# 08_RAM.net
KiCad netlist of a schematic drawn in Altium Designer
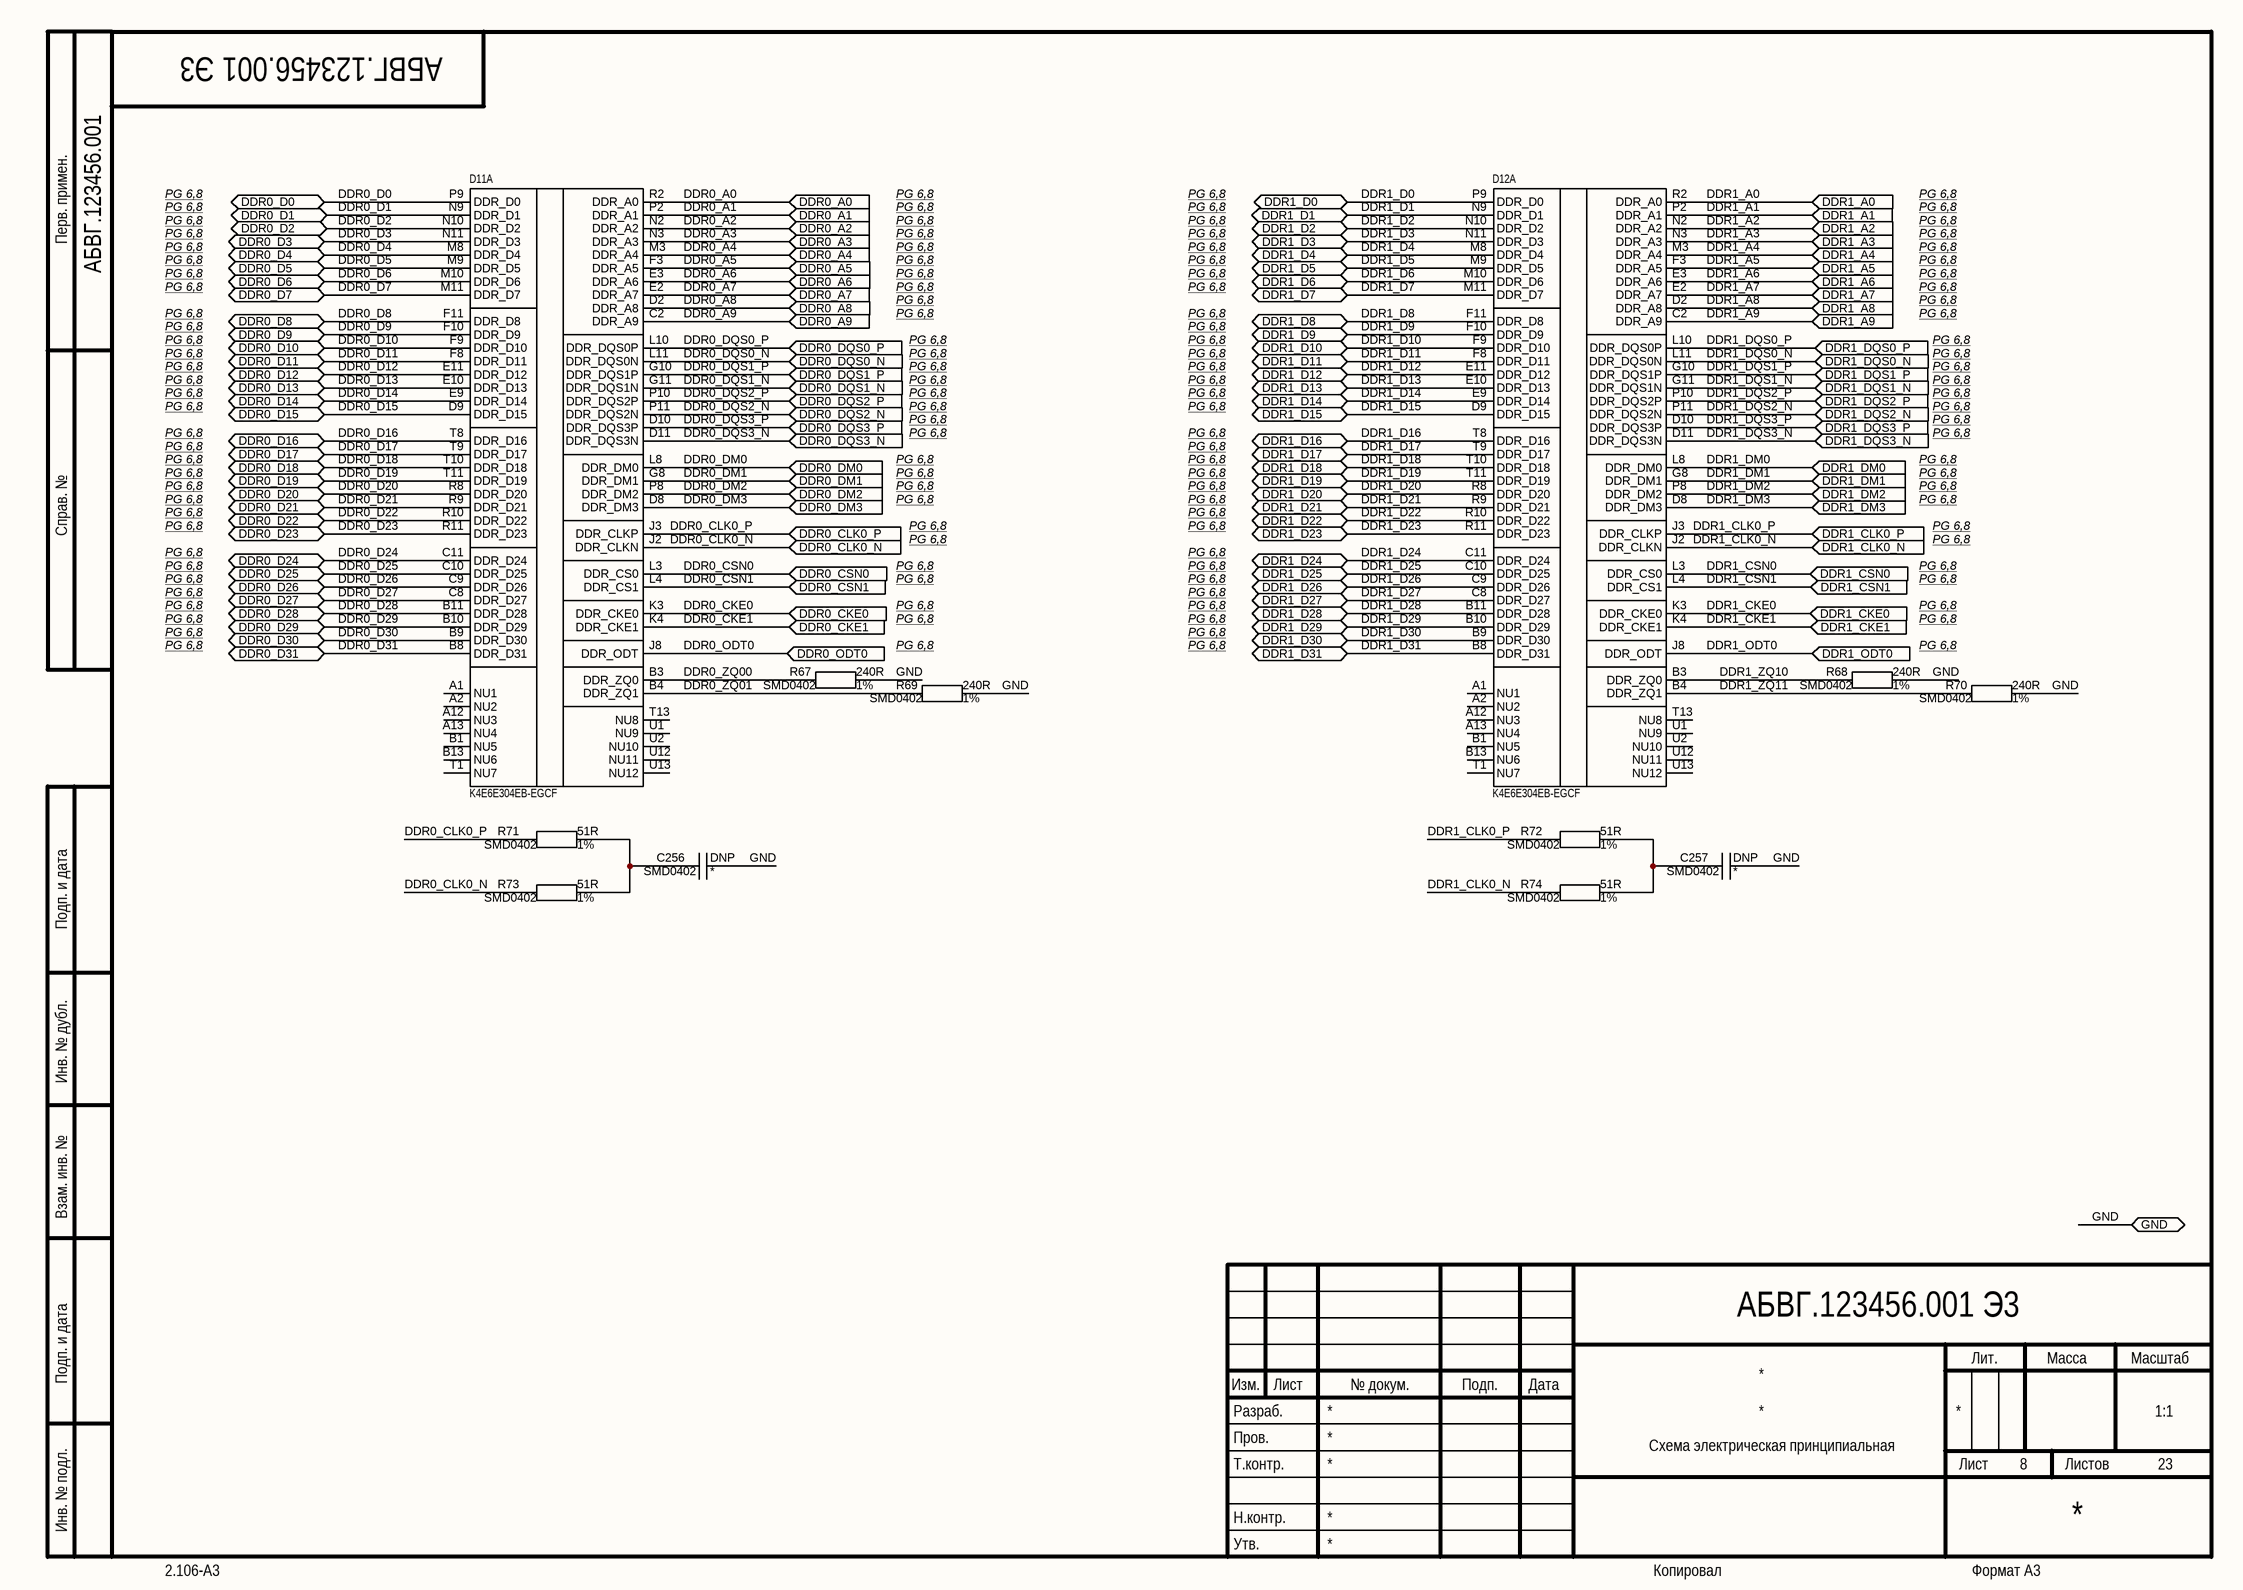
[diagram p0: 08 RAM.SchDoc]

(export (version "E")
  (design (tool "Eeschema 10.0.6"))
  (components
    (comp (ref "C256")
      (value "DNP")
      (footprint "Didur_PcbLib_1:CAP_SMD_0402_small")
      (fields
        (field (name "PACKAGE") "SMD0402")
        (field (name "PARTNUMBER") "Do Not Place")
        (field (name "VOLTAGE") "*")
      )
      (libsource (lib "Didur_SchLib_1") (part "Ceramic_Cap"))
    )
    (comp (ref "C257")
      (value "DNP")
      (footprint "Didur_PcbLib_1:CAP_SMD_0402_small")
      (fields
        (field (name "PACKAGE") "SMD0402")
        (field (name "PARTNUMBER") "Do Not Place")
        (field (name "VOLTAGE") "*")
      )
      (libsource (lib "Didur_SchLib_1") (part "Ceramic_Cap"))
    )
    (comp (ref "D11")
      (value "K4E6E304EB-EGCF")
      (footprint "Didur_PcbLib_1:FBGA178_13R00X11R50X1R20")
      (libsource (lib "Didur_SchLib_1") (part "K4E8E304EE-EGCE"))
    )
    (comp (ref "D12")
      (value "K4E6E304EB-EGCF")
      (footprint "Didur_PcbLib_1:FBGA178_13R00X11R50X1R20")
      (libsource (lib "Didur_SchLib_1") (part "K4E8E304EE-EGCE"))
    )
    (comp (ref "R67")
      (value "240R")
      (footprint "Didur_PcbLib_1:RES_SMD_0402_SMALL")
      (fields
        (field (name "PACKAGE") "SMD0402")
        (field (name "PARTNUMBER") "RC0402FR-07240RL")
        (field (name "TOLERANCE") "1%")
      )
      (libsource (lib "Didur_SchLib_1") (part "Chip_Res"))
    )
    (comp (ref "R68")
      (value "240R")
      (footprint "Didur_PcbLib_1:RES_SMD_0402_SMALL")
      (fields
        (field (name "PACKAGE") "SMD0402")
        (field (name "PARTNUMBER") "RC0402FR-07240RL")
        (field (name "TOLERANCE") "1%")
      )
      (libsource (lib "Didur_SchLib_1") (part "Chip_Res"))
    )
    (comp (ref "R69")
      (value "240R")
      (footprint "Didur_PcbLib_1:RES_SMD_0402_SMALL")
      (fields
        (field (name "PACKAGE") "SMD0402")
        (field (name "PARTNUMBER") "RC0402FR-07240RL")
        (field (name "TOLERANCE") "1%")
      )
      (libsource (lib "Didur_SchLib_1") (part "Chip_Res"))
    )
    (comp (ref "R70")
      (value "240R")
      (footprint "Didur_PcbLib_1:RES_SMD_0402_SMALL")
      (fields
        (field (name "PACKAGE") "SMD0402")
        (field (name "PARTNUMBER") "RC0402FR-07240RL")
        (field (name "TOLERANCE") "1%")
      )
      (libsource (lib "Didur_SchLib_1") (part "Chip_Res"))
    )
    (comp (ref "R71")
      (value "51R")
      (footprint "Didur_PcbLib_1:RES_SMD_0402_SMALL")
      (fields
        (field (name "PACKAGE") "SMD0402")
        (field (name "PARTNUMBER") "RC0402FR-0751RL")
        (field (name "TOLERANCE") "1%")
      )
      (libsource (lib "Didur_SchLib_1") (part "Chip_Res"))
    )
    (comp (ref "R72")
      (value "51R")
      (footprint "Didur_PcbLib_1:RES_SMD_0402_SMALL")
      (fields
        (field (name "PACKAGE") "SMD0402")
        (field (name "PARTNUMBER") "RC0402FR-0751RL")
        (field (name "TOLERANCE") "1%")
      )
      (libsource (lib "Didur_SchLib_1") (part "Chip_Res"))
    )
    (comp (ref "R73")
      (value "51R")
      (footprint "Didur_PcbLib_1:RES_SMD_0402_SMALL")
      (fields
        (field (name "PACKAGE") "SMD0402")
        (field (name "PARTNUMBER") "RC0402FR-0751RL")
        (field (name "TOLERANCE") "1%")
      )
      (libsource (lib "Didur_SchLib_1") (part "Chip_Res"))
    )
    (comp (ref "R74")
      (value "51R")
      (footprint "Didur_PcbLib_1:RES_SMD_0402_SMALL")
      (fields
        (field (name "PACKAGE") "SMD0402")
        (field (name "PARTNUMBER") "RC0402FR-0751RL")
        (field (name "TOLERANCE") "1%")
      )
      (libsource (lib "Didur_SchLib_1") (part "Chip_Res"))
    )
  )
  (nets
    (net (code "1") (name "/DDR0_A0") (class "Default")
      (node (ref "D11") (pin "R2") (pinfunction "DDR_A0_R2") (pintype "passive"))
    )
    (net (code "2") (name "/DDR0_A1") (class "Default")
      (node (ref "D11") (pin "P2") (pinfunction "DDR_A1_P2") (pintype "passive"))
    )
    (net (code "3") (name "/DDR0_A2") (class "Default")
      (node (ref "D11") (pin "N2") (pinfunction "DDR_A2_N2") (pintype "passive"))
    )
    (net (code "4") (name "/DDR0_A3") (class "Default")
      (node (ref "D11") (pin "N3") (pinfunction "DDR_A3_N3") (pintype "passive"))
    )
    (net (code "5") (name "/DDR0_A4") (class "Default")
      (node (ref "D11") (pin "M3") (pinfunction "DDR_A4_M3") (pintype "passive"))
    )
    (net (code "6") (name "/DDR0_A5") (class "Default")
      (node (ref "D11") (pin "F3") (pinfunction "DDR_A5_F3") (pintype "passive"))
    )
    (net (code "7") (name "/DDR0_A6") (class "Default")
      (node (ref "D11") (pin "E3") (pinfunction "DDR_A6_E3") (pintype "passive"))
    )
    (net (code "8") (name "/DDR0_A7") (class "Default")
      (node (ref "D11") (pin "E2") (pinfunction "DDR_A7_E2") (pintype "passive"))
    )
    (net (code "9") (name "/DDR0_A8") (class "Default")
      (node (ref "D11") (pin "D2") (pinfunction "DDR_A8_D2") (pintype "passive"))
    )
    (net (code "10") (name "/DDR0_A9") (class "Default")
      (node (ref "D11") (pin "C2") (pinfunction "DDR_A9_C2") (pintype "passive"))
    )
    (net (code "11") (name "/DDR0_CKE0") (class "Default")
      (node (ref "D11") (pin "K3") (pinfunction "DDR_CKE0_K3") (pintype "passive"))
    )
    (net (code "12") (name "/DDR0_CKE1") (class "Default")
      (node (ref "D11") (pin "K4") (pinfunction "DDR_CKE1_K4") (pintype "passive"))
    )
    (net (code "13") (name "/DDR0_CLK0_N") (class "Default")
      (node (ref "D11") (pin "J2") (pinfunction "DDR_CLKN_J2") (pintype "passive"))
      (node (ref "R73") (pin "2") (pinfunction "2_2") (pintype "passive"))
    )
    (net (code "14") (name "/DDR0_CLK0_P") (class "Default")
      (node (ref "D11") (pin "J3") (pinfunction "DDR_CLKP_J3") (pintype "passive"))
      (node (ref "R71") (pin "2") (pinfunction "2_2") (pintype "passive"))
    )
    (net (code "15") (name "/DDR0_CSN0") (class "Default")
      (node (ref "D11") (pin "L3") (pinfunction "DDR_CS0_L3") (pintype "passive"))
    )
    (net (code "16") (name "/DDR0_CSN1") (class "Default")
      (node (ref "D11") (pin "L4") (pinfunction "DDR_CS1_L4") (pintype "passive"))
    )
    (net (code "17") (name "/DDR0_D0") (class "Default")
      (node (ref "D11") (pin "P9") (pinfunction "DDR_D0_P9") (pintype "passive"))
    )
    (net (code "18") (name "/DDR0_D1") (class "Default")
      (node (ref "D11") (pin "N9") (pinfunction "DDR_D1_N9") (pintype "passive"))
    )
    (net (code "19") (name "/DDR0_D2") (class "Default")
      (node (ref "D11") (pin "N10") (pinfunction "DDR_D2_N10") (pintype "passive"))
    )
    (net (code "20") (name "/DDR0_D3") (class "Default")
      (node (ref "D11") (pin "N11") (pinfunction "DDR_D3_N11") (pintype "passive"))
    )
    (net (code "21") (name "/DDR0_D4") (class "Default")
      (node (ref "D11") (pin "M8") (pinfunction "DDR_D4_M8") (pintype "passive"))
    )
    (net (code "22") (name "/DDR0_D5") (class "Default")
      (node (ref "D11") (pin "M9") (pinfunction "DDR_D5_M9") (pintype "passive"))
    )
    (net (code "23") (name "/DDR0_D6") (class "Default")
      (node (ref "D11") (pin "M10") (pinfunction "DDR_D6_M10") (pintype "passive"))
    )
    (net (code "24") (name "/DDR0_D7") (class "Default")
      (node (ref "D11") (pin "M11") (pinfunction "DDR_D7_M11") (pintype "passive"))
    )
    (net (code "25") (name "/DDR0_D8") (class "Default")
      (node (ref "D11") (pin "F11") (pinfunction "DDR_D8_F11") (pintype "passive"))
    )
    (net (code "26") (name "/DDR0_D9") (class "Default")
      (node (ref "D11") (pin "F10") (pinfunction "DDR_D9_F10") (pintype "passive"))
    )
    (net (code "27") (name "/DDR0_D10") (class "Default")
      (node (ref "D11") (pin "F9") (pinfunction "DDR_D10_F9") (pintype "passive"))
    )
    (net (code "28") (name "/DDR0_D11") (class "Default")
      (node (ref "D11") (pin "F8") (pinfunction "DDR_D11_F8") (pintype "passive"))
    )
    (net (code "29") (name "/DDR0_D12") (class "Default")
      (node (ref "D11") (pin "E11") (pinfunction "DDR_D12_E11") (pintype "passive"))
    )
    (net (code "30") (name "/DDR0_D13") (class "Default")
      (node (ref "D11") (pin "E10") (pinfunction "DDR_D13_E10") (pintype "passive"))
    )
    (net (code "31") (name "/DDR0_D14") (class "Default")
      (node (ref "D11") (pin "E9") (pinfunction "DDR_D14_E9") (pintype "passive"))
    )
    (net (code "32") (name "/DDR0_D15") (class "Default")
      (node (ref "D11") (pin "D9") (pinfunction "DDR_D15_D9") (pintype "passive"))
    )
    (net (code "33") (name "/DDR0_D16") (class "Default")
      (node (ref "D11") (pin "T8") (pinfunction "DDR_D16_T8") (pintype "passive"))
    )
    (net (code "34") (name "/DDR0_D17") (class "Default")
      (node (ref "D11") (pin "T9") (pinfunction "DDR_D17_T9") (pintype "passive"))
    )
    (net (code "35") (name "/DDR0_D18") (class "Default")
      (node (ref "D11") (pin "T10") (pinfunction "DDR_D18_T10") (pintype "passive"))
    )
    (net (code "36") (name "/DDR0_D19") (class "Default")
      (node (ref "D11") (pin "T11") (pinfunction "DDR_D19_T11") (pintype "passive"))
    )
    (net (code "37") (name "/DDR0_D20") (class "Default")
      (node (ref "D11") (pin "R8") (pinfunction "DDR_D20_R8") (pintype "passive"))
    )
    (net (code "38") (name "/DDR0_D21") (class "Default")
      (node (ref "D11") (pin "R9") (pinfunction "DDR_D21_R9") (pintype "passive"))
    )
    (net (code "39") (name "/DDR0_D22") (class "Default")
      (node (ref "D11") (pin "R10") (pinfunction "DDR_D22_R10") (pintype "passive"))
    )
    (net (code "40") (name "/DDR0_D23") (class "Default")
      (node (ref "D11") (pin "R11") (pinfunction "DDR_D23_R11") (pintype "passive"))
    )
    (net (code "41") (name "/DDR0_D24") (class "Default")
      (node (ref "D11") (pin "C11") (pinfunction "DDR_D24_C11") (pintype "passive"))
    )
    (net (code "42") (name "/DDR0_D25") (class "Default")
      (node (ref "D11") (pin "C10") (pinfunction "DDR_D25_C10") (pintype "passive"))
    )
    (net (code "43") (name "/DDR0_D26") (class "Default")
      (node (ref "D11") (pin "C9") (pinfunction "DDR_D26_C9") (pintype "passive"))
    )
    (net (code "44") (name "/DDR0_D27") (class "Default")
      (node (ref "D11") (pin "C8") (pinfunction "DDR_D27_C8") (pintype "passive"))
    )
    (net (code "45") (name "/DDR0_D28") (class "Default")
      (node (ref "D11") (pin "B11") (pinfunction "DDR_D28_B11") (pintype "passive"))
    )
    (net (code "46") (name "/DDR0_D29") (class "Default")
      (node (ref "D11") (pin "B10") (pinfunction "DDR_D29_B10") (pintype "passive"))
    )
    (net (code "47") (name "/DDR0_D30") (class "Default")
      (node (ref "D11") (pin "B9") (pinfunction "DDR_D30_B9") (pintype "passive"))
    )
    (net (code "48") (name "/DDR0_D31") (class "Default")
      (node (ref "D11") (pin "B8") (pinfunction "DDR_D31_B8") (pintype "passive"))
    )
    (net (code "49") (name "/DDR0_DM0") (class "Default")
      (node (ref "D11") (pin "L8") (pinfunction "DDR_DM0_L8") (pintype "passive"))
    )
    (net (code "50") (name "/DDR0_DM1") (class "Default")
      (node (ref "D11") (pin "G8") (pinfunction "DDR_DM1_G8") (pintype "passive"))
    )
    (net (code "51") (name "/DDR0_DM2") (class "Default")
      (node (ref "D11") (pin "P8") (pinfunction "DDR_DM2_P8") (pintype "passive"))
    )
    (net (code "52") (name "/DDR0_DM3") (class "Default")
      (node (ref "D11") (pin "D8") (pinfunction "DDR_DM3_D8") (pintype "passive"))
    )
    (net (code "53") (name "/DDR0_DQS0_N") (class "Default")
      (node (ref "D11") (pin "L11") (pinfunction "DDR_DQS0N_L11") (pintype "passive"))
    )
    (net (code "54") (name "/DDR0_DQS0_P") (class "Default")
      (node (ref "D11") (pin "L10") (pinfunction "DDR_DQS0P_L10") (pintype "passive"))
    )
    (net (code "55") (name "/DDR0_DQS1_N") (class "Default")
      (node (ref "D11") (pin "G11") (pinfunction "DDR_DQS1N_G11") (pintype "passive"))
    )
    (net (code "56") (name "/DDR0_DQS1_P") (class "Default")
      (node (ref "D11") (pin "G10") (pinfunction "DDR_DQS1P_G10") (pintype "passive"))
    )
    (net (code "57") (name "/DDR0_DQS2_N") (class "Default")
      (node (ref "D11") (pin "P11") (pinfunction "DDR_DQS2N_P11") (pintype "passive"))
    )
    (net (code "58") (name "/DDR0_DQS2_P") (class "Default")
      (node (ref "D11") (pin "P10") (pinfunction "DDR_DQS2P_P10") (pintype "passive"))
    )
    (net (code "59") (name "/DDR0_DQS3_N") (class "Default")
      (node (ref "D11") (pin "D11") (pinfunction "DDR_DQS3N_D11") (pintype "passive"))
    )
    (net (code "60") (name "/DDR0_DQS3_P") (class "Default")
      (node (ref "D11") (pin "D10") (pinfunction "DDR_DQS3P_D10") (pintype "passive"))
    )
    (net (code "61") (name "/DDR0_ODT0") (class "Default")
      (node (ref "D11") (pin "J8") (pinfunction "DDR_ODT_J8") (pintype "passive"))
    )
    (net (code "62") (name "/DDR0_ZQ00") (class "Default")
      (node (ref "D11") (pin "B3") (pinfunction "DDR_ZQ0_B3") (pintype "passive"))
      (node (ref "R67") (pin "2") (pinfunction "2_2") (pintype "passive"))
    )
    (net (code "63") (name "/DDR0_ZQ01") (class "Default")
      (node (ref "D11") (pin "B4") (pinfunction "DDR_ZQ1_B4") (pintype "passive"))
      (node (ref "R69") (pin "2") (pinfunction "2_2") (pintype "passive"))
    )
    (net (code "64") (name "/DDR1_A0") (class "Default")
      (node (ref "D12") (pin "R2") (pinfunction "DDR_A0_R2") (pintype "passive"))
    )
    (net (code "65") (name "/DDR1_A1") (class "Default")
      (node (ref "D12") (pin "P2") (pinfunction "DDR_A1_P2") (pintype "passive"))
    )
    (net (code "66") (name "/DDR1_A2") (class "Default")
      (node (ref "D12") (pin "N2") (pinfunction "DDR_A2_N2") (pintype "passive"))
    )
    (net (code "67") (name "/DDR1_A3") (class "Default")
      (node (ref "D12") (pin "N3") (pinfunction "DDR_A3_N3") (pintype "passive"))
    )
    (net (code "68") (name "/DDR1_A4") (class "Default")
      (node (ref "D12") (pin "M3") (pinfunction "DDR_A4_M3") (pintype "passive"))
    )
    (net (code "69") (name "/DDR1_A5") (class "Default")
      (node (ref "D12") (pin "F3") (pinfunction "DDR_A5_F3") (pintype "passive"))
    )
    (net (code "70") (name "/DDR1_A6") (class "Default")
      (node (ref "D12") (pin "E3") (pinfunction "DDR_A6_E3") (pintype "passive"))
    )
    (net (code "71") (name "/DDR1_A7") (class "Default")
      (node (ref "D12") (pin "E2") (pinfunction "DDR_A7_E2") (pintype "passive"))
    )
    (net (code "72") (name "/DDR1_A8") (class "Default")
      (node (ref "D12") (pin "D2") (pinfunction "DDR_A8_D2") (pintype "passive"))
    )
    (net (code "73") (name "/DDR1_A9") (class "Default")
      (node (ref "D12") (pin "C2") (pinfunction "DDR_A9_C2") (pintype "passive"))
    )
    (net (code "74") (name "/DDR1_CKE0") (class "Default")
      (node (ref "D12") (pin "K3") (pinfunction "DDR_CKE0_K3") (pintype "passive"))
    )
    (net (code "75") (name "/DDR1_CKE1") (class "Default")
      (node (ref "D12") (pin "K4") (pinfunction "DDR_CKE1_K4") (pintype "passive"))
    )
    (net (code "76") (name "/DDR1_CLK0_N") (class "Default")
      (node (ref "D12") (pin "J2") (pinfunction "DDR_CLKN_J2") (pintype "passive"))
      (node (ref "R74") (pin "2") (pinfunction "2_2") (pintype "passive"))
    )
    (net (code "77") (name "/DDR1_CLK0_P") (class "Default")
      (node (ref "D12") (pin "J3") (pinfunction "DDR_CLKP_J3") (pintype "passive"))
      (node (ref "R72") (pin "2") (pinfunction "2_2") (pintype "passive"))
    )
    (net (code "78") (name "/DDR1_CSN0") (class "Default")
      (node (ref "D12") (pin "L3") (pinfunction "DDR_CS0_L3") (pintype "passive"))
    )
    (net (code "79") (name "/DDR1_CSN1") (class "Default")
      (node (ref "D12") (pin "L4") (pinfunction "DDR_CS1_L4") (pintype "passive"))
    )
    (net (code "80") (name "/DDR1_D0") (class "Default")
      (node (ref "D12") (pin "P9") (pinfunction "DDR_D0_P9") (pintype "passive"))
    )
    (net (code "81") (name "/DDR1_D1") (class "Default")
      (node (ref "D12") (pin "N9") (pinfunction "DDR_D1_N9") (pintype "passive"))
    )
    (net (code "82") (name "/DDR1_D2") (class "Default")
      (node (ref "D12") (pin "N10") (pinfunction "DDR_D2_N10") (pintype "passive"))
    )
    (net (code "83") (name "/DDR1_D3") (class "Default")
      (node (ref "D12") (pin "N11") (pinfunction "DDR_D3_N11") (pintype "passive"))
    )
    (net (code "84") (name "/DDR1_D4") (class "Default")
      (node (ref "D12") (pin "M8") (pinfunction "DDR_D4_M8") (pintype "passive"))
    )
    (net (code "85") (name "/DDR1_D5") (class "Default")
      (node (ref "D12") (pin "M9") (pinfunction "DDR_D5_M9") (pintype "passive"))
    )
    (net (code "86") (name "/DDR1_D6") (class "Default")
      (node (ref "D12") (pin "M10") (pinfunction "DDR_D6_M10") (pintype "passive"))
    )
    (net (code "87") (name "/DDR1_D7") (class "Default")
      (node (ref "D12") (pin "M11") (pinfunction "DDR_D7_M11") (pintype "passive"))
    )
    (net (code "88") (name "/DDR1_D8") (class "Default")
      (node (ref "D12") (pin "F11") (pinfunction "DDR_D8_F11") (pintype "passive"))
    )
    (net (code "89") (name "/DDR1_D9") (class "Default")
      (node (ref "D12") (pin "F10") (pinfunction "DDR_D9_F10") (pintype "passive"))
    )
    (net (code "90") (name "/DDR1_D10") (class "Default")
      (node (ref "D12") (pin "F9") (pinfunction "DDR_D10_F9") (pintype "passive"))
    )
    (net (code "91") (name "/DDR1_D11") (class "Default")
      (node (ref "D12") (pin "F8") (pinfunction "DDR_D11_F8") (pintype "passive"))
    )
    (net (code "92") (name "/DDR1_D12") (class "Default")
      (node (ref "D12") (pin "E11") (pinfunction "DDR_D12_E11") (pintype "passive"))
    )
    (net (code "93") (name "/DDR1_D13") (class "Default")
      (node (ref "D12") (pin "E10") (pinfunction "DDR_D13_E10") (pintype "passive"))
    )
    (net (code "94") (name "/DDR1_D14") (class "Default")
      (node (ref "D12") (pin "E9") (pinfunction "DDR_D14_E9") (pintype "passive"))
    )
    (net (code "95") (name "/DDR1_D15") (class "Default")
      (node (ref "D12") (pin "D9") (pinfunction "DDR_D15_D9") (pintype "passive"))
    )
    (net (code "96") (name "/DDR1_D16") (class "Default")
      (node (ref "D12") (pin "T8") (pinfunction "DDR_D16_T8") (pintype "passive"))
    )
    (net (code "97") (name "/DDR1_D17") (class "Default")
      (node (ref "D12") (pin "T9") (pinfunction "DDR_D17_T9") (pintype "passive"))
    )
    (net (code "98") (name "/DDR1_D18") (class "Default")
      (node (ref "D12") (pin "T10") (pinfunction "DDR_D18_T10") (pintype "passive"))
    )
    (net (code "99") (name "/DDR1_D19") (class "Default")
      (node (ref "D12") (pin "T11") (pinfunction "DDR_D19_T11") (pintype "passive"))
    )
    (net (code "100") (name "/DDR1_D20") (class "Default")
      (node (ref "D12") (pin "R8") (pinfunction "DDR_D20_R8") (pintype "passive"))
    )
    (net (code "101") (name "/DDR1_D21") (class "Default")
      (node (ref "D12") (pin "R9") (pinfunction "DDR_D21_R9") (pintype "passive"))
    )
    (net (code "102") (name "/DDR1_D22") (class "Default")
      (node (ref "D12") (pin "R10") (pinfunction "DDR_D22_R10") (pintype "passive"))
    )
    (net (code "103") (name "/DDR1_D23") (class "Default")
      (node (ref "D12") (pin "R11") (pinfunction "DDR_D23_R11") (pintype "passive"))
    )
    (net (code "104") (name "/DDR1_D24") (class "Default")
      (node (ref "D12") (pin "C11") (pinfunction "DDR_D24_C11") (pintype "passive"))
    )
    (net (code "105") (name "/DDR1_D25") (class "Default")
      (node (ref "D12") (pin "C10") (pinfunction "DDR_D25_C10") (pintype "passive"))
    )
    (net (code "106") (name "/DDR1_D26") (class "Default")
      (node (ref "D12") (pin "C9") (pinfunction "DDR_D26_C9") (pintype "passive"))
    )
    (net (code "107") (name "/DDR1_D27") (class "Default")
      (node (ref "D12") (pin "C8") (pinfunction "DDR_D27_C8") (pintype "passive"))
    )
    (net (code "108") (name "/DDR1_D28") (class "Default")
      (node (ref "D12") (pin "B11") (pinfunction "DDR_D28_B11") (pintype "passive"))
    )
    (net (code "109") (name "/DDR1_D29") (class "Default")
      (node (ref "D12") (pin "B10") (pinfunction "DDR_D29_B10") (pintype "passive"))
    )
    (net (code "110") (name "/DDR1_D30") (class "Default")
      (node (ref "D12") (pin "B9") (pinfunction "DDR_D30_B9") (pintype "passive"))
    )
    (net (code "111") (name "/DDR1_D31") (class "Default")
      (node (ref "D12") (pin "B8") (pinfunction "DDR_D31_B8") (pintype "passive"))
    )
    (net (code "112") (name "/DDR1_DM0") (class "Default")
      (node (ref "D12") (pin "L8") (pinfunction "DDR_DM0_L8") (pintype "passive"))
    )
    (net (code "113") (name "/DDR1_DM1") (class "Default")
      (node (ref "D12") (pin "G8") (pinfunction "DDR_DM1_G8") (pintype "passive"))
    )
    (net (code "114") (name "/DDR1_DM2") (class "Default")
      (node (ref "D12") (pin "P8") (pinfunction "DDR_DM2_P8") (pintype "passive"))
    )
    (net (code "115") (name "/DDR1_DM3") (class "Default")
      (node (ref "D12") (pin "D8") (pinfunction "DDR_DM3_D8") (pintype "passive"))
    )
    (net (code "116") (name "/DDR1_DQS0_N") (class "Default")
      (node (ref "D12") (pin "L11") (pinfunction "DDR_DQS0N_L11") (pintype "passive"))
    )
    (net (code "117") (name "/DDR1_DQS0_P") (class "Default")
      (node (ref "D12") (pin "L10") (pinfunction "DDR_DQS0P_L10") (pintype "passive"))
    )
    (net (code "118") (name "/DDR1_DQS1_N") (class "Default")
      (node (ref "D12") (pin "G11") (pinfunction "DDR_DQS1N_G11") (pintype "passive"))
    )
    (net (code "119") (name "/DDR1_DQS1_P") (class "Default")
      (node (ref "D12") (pin "G10") (pinfunction "DDR_DQS1P_G10") (pintype "passive"))
    )
    (net (code "120") (name "/DDR1_DQS2_N") (class "Default")
      (node (ref "D12") (pin "P11") (pinfunction "DDR_DQS2N_P11") (pintype "passive"))
    )
    (net (code "121") (name "/DDR1_DQS2_P") (class "Default")
      (node (ref "D12") (pin "P10") (pinfunction "DDR_DQS2P_P10") (pintype "passive"))
    )
    (net (code "122") (name "/DDR1_DQS3_N") (class "Default")
      (node (ref "D12") (pin "D11") (pinfunction "DDR_DQS3N_D11") (pintype "passive"))
    )
    (net (code "123") (name "/DDR1_DQS3_P") (class "Default")
      (node (ref "D12") (pin "D10") (pinfunction "DDR_DQS3P_D10") (pintype "passive"))
    )
    (net (code "124") (name "/DDR1_ODT0") (class "Default")
      (node (ref "D12") (pin "J8") (pinfunction "DDR_ODT_J8") (pintype "passive"))
    )
    (net (code "125") (name "/DDR1_ZQ10") (class "Default")
      (node (ref "D12") (pin "B3") (pinfunction "DDR_ZQ0_B3") (pintype "passive"))
      (node (ref "R68") (pin "2") (pinfunction "2_2") (pintype "passive"))
    )
    (net (code "126") (name "/DDR1_ZQ11") (class "Default")
      (node (ref "D12") (pin "B4") (pinfunction "DDR_ZQ1_B4") (pintype "passive"))
      (node (ref "R70") (pin "2") (pinfunction "2_2") (pintype "passive"))
    )
    (net (code "127") (name "/GND") (class "Default")
      (node (ref "C256") (pin "1") (pinfunction "1_1") (pintype "power_in"))
      (node (ref "C257") (pin "1") (pinfunction "1_1") (pintype "power_in"))
      (node (ref "R67") (pin "1") (pinfunction "1_1") (pintype "passive"))
      (node (ref "R68") (pin "1") (pinfunction "1_1") (pintype "passive"))
      (node (ref "R69") (pin "1") (pinfunction "1_1") (pintype "passive"))
      (node (ref "R70") (pin "1") (pinfunction "1_1") (pintype "passive"))
    )
    (net (code "128") (name "Net-(C256-Pad2)") (class "Default")
      (node (ref "C256") (pin "2") (pinfunction "2_2") (pintype "power_in"))
      (node (ref "R71") (pin "1") (pinfunction "1_1") (pintype "passive"))
      (node (ref "R73") (pin "1") (pinfunction "1_1") (pintype "passive"))
    )
    (net (code "129") (name "Net-(C257-Pad2)") (class "Default")
      (node (ref "C257") (pin "2") (pinfunction "2_2") (pintype "power_in"))
      (node (ref "R72") (pin "1") (pinfunction "1_1") (pintype "passive"))
      (node (ref "R74") (pin "1") (pinfunction "1_1") (pintype "passive"))
    )
    (net (code "130") (name "unconnected-(D11A-NU1-PadA1)") (class "Default")
      (node (ref "D11") (pin "A1") (pinfunction "NU1_A1") (pintype "passive"))
    )
    (net (code "131") (name "unconnected-(D11A-NU2-PadA2)") (class "Default")
      (node (ref "D11") (pin "A2") (pinfunction "NU2_A2") (pintype "passive"))
    )
    (net (code "132") (name "unconnected-(D11A-NU3-PadA12)") (class "Default")
      (node (ref "D11") (pin "A12") (pinfunction "NU3_A12") (pintype "passive"))
    )
    (net (code "133") (name "unconnected-(D11A-NU4-PadA13)") (class "Default")
      (node (ref "D11") (pin "A13") (pinfunction "NU4_A13") (pintype "passive"))
    )
    (net (code "134") (name "unconnected-(D11A-NU5-PadB1)") (class "Default")
      (node (ref "D11") (pin "B1") (pinfunction "NU5_B1") (pintype "passive"))
    )
    (net (code "135") (name "unconnected-(D11A-NU6-PadB13)") (class "Default")
      (node (ref "D11") (pin "B13") (pinfunction "NU6_B13") (pintype "passive"))
    )
    (net (code "136") (name "unconnected-(D11A-NU7-PadT1)") (class "Default")
      (node (ref "D11") (pin "T1") (pinfunction "NU7_T1") (pintype "passive"))
    )
    (net (code "137") (name "unconnected-(D11A-NU8-PadT13)") (class "Default")
      (node (ref "D11") (pin "T13") (pinfunction "NU8_T13") (pintype "passive"))
    )
    (net (code "138") (name "unconnected-(D11A-NU9-PadU1)") (class "Default")
      (node (ref "D11") (pin "U1") (pinfunction "NU9_U1") (pintype "passive"))
    )
    (net (code "139") (name "unconnected-(D11A-NU10-PadU2)") (class "Default")
      (node (ref "D11") (pin "U2") (pinfunction "NU10_U2") (pintype "passive"))
    )
    (net (code "140") (name "unconnected-(D11A-NU11-PadU12)") (class "Default")
      (node (ref "D11") (pin "U12") (pinfunction "NU11_U12") (pintype "passive"))
    )
    (net (code "141") (name "unconnected-(D11A-NU12-PadU13)") (class "Default")
      (node (ref "D11") (pin "U13") (pinfunction "NU12_U13") (pintype "passive"))
    )
    (net (code "142") (name "unconnected-(D12A-NU1-PadA1)") (class "Default")
      (node (ref "D12") (pin "A1") (pinfunction "NU1_A1") (pintype "passive"))
    )
    (net (code "143") (name "unconnected-(D12A-NU2-PadA2)") (class "Default")
      (node (ref "D12") (pin "A2") (pinfunction "NU2_A2") (pintype "passive"))
    )
    (net (code "144") (name "unconnected-(D12A-NU3-PadA12)") (class "Default")
      (node (ref "D12") (pin "A12") (pinfunction "NU3_A12") (pintype "passive"))
    )
    (net (code "145") (name "unconnected-(D12A-NU4-PadA13)") (class "Default")
      (node (ref "D12") (pin "A13") (pinfunction "NU4_A13") (pintype "passive"))
    )
    (net (code "146") (name "unconnected-(D12A-NU5-PadB1)") (class "Default")
      (node (ref "D12") (pin "B1") (pinfunction "NU5_B1") (pintype "passive"))
    )
    (net (code "147") (name "unconnected-(D12A-NU6-PadB13)") (class "Default")
      (node (ref "D12") (pin "B13") (pinfunction "NU6_B13") (pintype "passive"))
    )
    (net (code "148") (name "unconnected-(D12A-NU7-PadT1)") (class "Default")
      (node (ref "D12") (pin "T1") (pinfunction "NU7_T1") (pintype "passive"))
    )
    (net (code "149") (name "unconnected-(D12A-NU8-PadT13)") (class "Default")
      (node (ref "D12") (pin "T13") (pinfunction "NU8_T13") (pintype "passive"))
    )
    (net (code "150") (name "unconnected-(D12A-NU9-PadU1)") (class "Default")
      (node (ref "D12") (pin "U1") (pinfunction "NU9_U1") (pintype "passive"))
    )
    (net (code "151") (name "unconnected-(D12A-NU10-PadU2)") (class "Default")
      (node (ref "D12") (pin "U2") (pinfunction "NU10_U2") (pintype "passive"))
    )
    (net (code "152") (name "unconnected-(D12A-NU11-PadU12)") (class "Default")
      (node (ref "D12") (pin "U12") (pinfunction "NU11_U12") (pintype "passive"))
    )
    (net (code "153") (name "unconnected-(D12A-NU12-PadU13)") (class "Default")
      (node (ref "D12") (pin "U13") (pinfunction "NU12_U13") (pintype "passive"))
    )
  )
)
